# 1_P1.net
KiCad netlist of a schematic drawn in Altium Designer
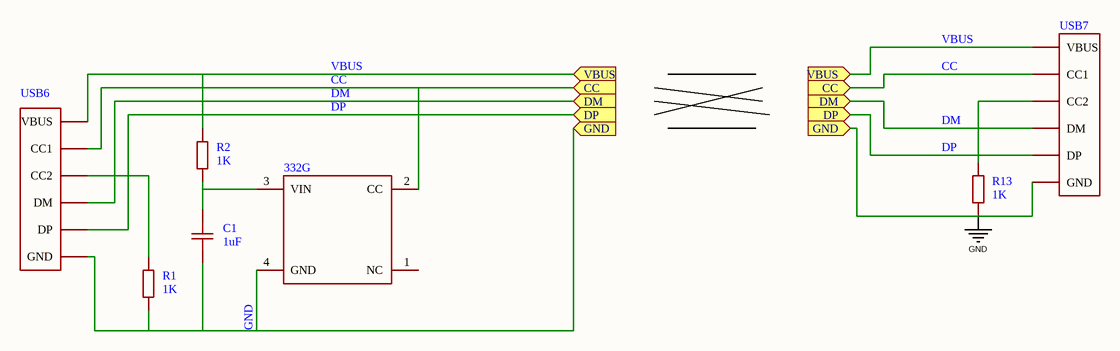
[diagram p0: 1_P1.schdoc]

(export (version "E")
  (design (tool "Eeschema 10.0.6"))
  (components
    (comp (ref "332G")
      (value "~")
      (footprint "ODFN-4_L1.6-W1.6")
      (libsource (lib "altium-import") (part "root_2_332G_"))
    )
    (comp (ref "C1") (value "1uF") (footprint "0603C") (libsource (lib "altium-import") (part "root_3_1uF_")))
    (comp (ref "R1")
      (value "1K")
      (footprint "0603R")
      (fields (field (name "ALTIUM_VALUE") "1K"))
      (libsource (lib "altium-import") (part "root_1_10K_"))
    )
    (comp (ref "R2")
      (value "1K")
      (footprint "R0603")
      (libsource (lib "altium-import") (part "root_1_Res_0603_"))
    )
    (comp (ref "R13")
      (value "1K")
      (footprint "0603R")
      (fields (field (name "ALTIUM_VALUE") "1K"))
      (libsource (lib "altium-import") (part "root_1_10K_"))
    )
    (comp (ref "USB6")
      (value "~")
      (footprint "TYPE-C14P")
      (libsource (lib "altium-import") (part "root_0_mirrored_TYPEC-14PIN(公头）_"))
    )
    (comp (ref "USB7")
      (value "~")
      (footprint "TYPE-C14P")
      (libsource (lib "altium-import") (part "root_0_TYPEC-14PIN(公头）_"))
    )
  )
  (nets
    (net (code "1") (name "/CC") (class "Default")
      (node (ref "332G") (pin "2") (pinfunction "CC_2") (pintype "passive"))
      (node (ref "USB6") (pin "CC1") (pinfunction "CC1_CC1") (pintype "passive"))
      (node (ref "USB7") (pin "CC1") (pinfunction "CC1_CC1") (pintype "passive"))
    )
    (net (code "2") (name "/DM") (class "Default")
      (node (ref "USB6") (pin "DM") (pinfunction "DM_DM") (pintype "passive"))
      (node (ref "USB7") (pin "DM") (pinfunction "DM_DM") (pintype "passive"))
    )
    (net (code "3") (name "/DP") (class "Default")
      (node (ref "USB6") (pin "DP") (pinfunction "DP_DP") (pintype "passive"))
      (node (ref "USB7") (pin "DP") (pinfunction "DP_DP") (pintype "passive"))
    )
    (net (code "4") (name "/VBUS") (class "Default")
      (node (ref "R2") (pin "2") (pinfunction "2_2") (pintype "passive"))
      (node (ref "USB6") (pin "VBUS") (pinfunction "VBUS_VBUS") (pintype "passive"))
      (node (ref "USB7") (pin "VBUS") (pinfunction "VBUS_VBUS") (pintype "passive"))
    )
    (net (code "5") (name "GND") (class "Default")
      (node (ref "332G") (pin "4") (pinfunction "GND_4") (pintype "passive"))
      (node (ref "C1") (pin "2") (pinfunction "2_2") (pintype "passive"))
      (node (ref "R1") (pin "1") (pinfunction "1_1") (pintype "passive"))
      (node (ref "R13") (pin "1") (pinfunction "1_1") (pintype "passive"))
      (node (ref "USB6") (pin "GND") (pinfunction "GND_GND") (pintype "passive"))
      (node (ref "USB7") (pin "GND") (pinfunction "GND_GND") (pintype "passive"))
    )
    (net (code "6") (name "Net-(332G-VIN)") (class "Default")
      (node (ref "332G") (pin "3") (pinfunction "VIN_3") (pintype "passive"))
      (node (ref "C1") (pin "1") (pinfunction "1_1") (pintype "passive"))
      (node (ref "R2") (pin "1") (pinfunction "1_1") (pintype "passive"))
    )
    (net (code "7") (name "Net-(R1-Pad2)") (class "Default")
      (node (ref "R1") (pin "2") (pinfunction "2_2") (pintype "passive"))
      (node (ref "USB6") (pin "CC2") (pinfunction "CC2_CC2") (pintype "passive"))
    )
    (net (code "8") (name "Net-(R13-Pad2)") (class "Default")
      (node (ref "R13") (pin "2") (pinfunction "2_2") (pintype "passive"))
      (node (ref "USB7") (pin "CC2") (pinfunction "CC2_CC2") (pintype "passive"))
    )
    (net (code "9") (name "unconnected-(332G-NC-Pad1)") (class "Default")
      (node (ref "332G") (pin "1") (pinfunction "NC_1") (pintype "passive"))
    )
  )
)
